# axiom_beta_plugin_module_eMMC_v0_1.net
KiCad netlist of a schematic drawn in EAGLE
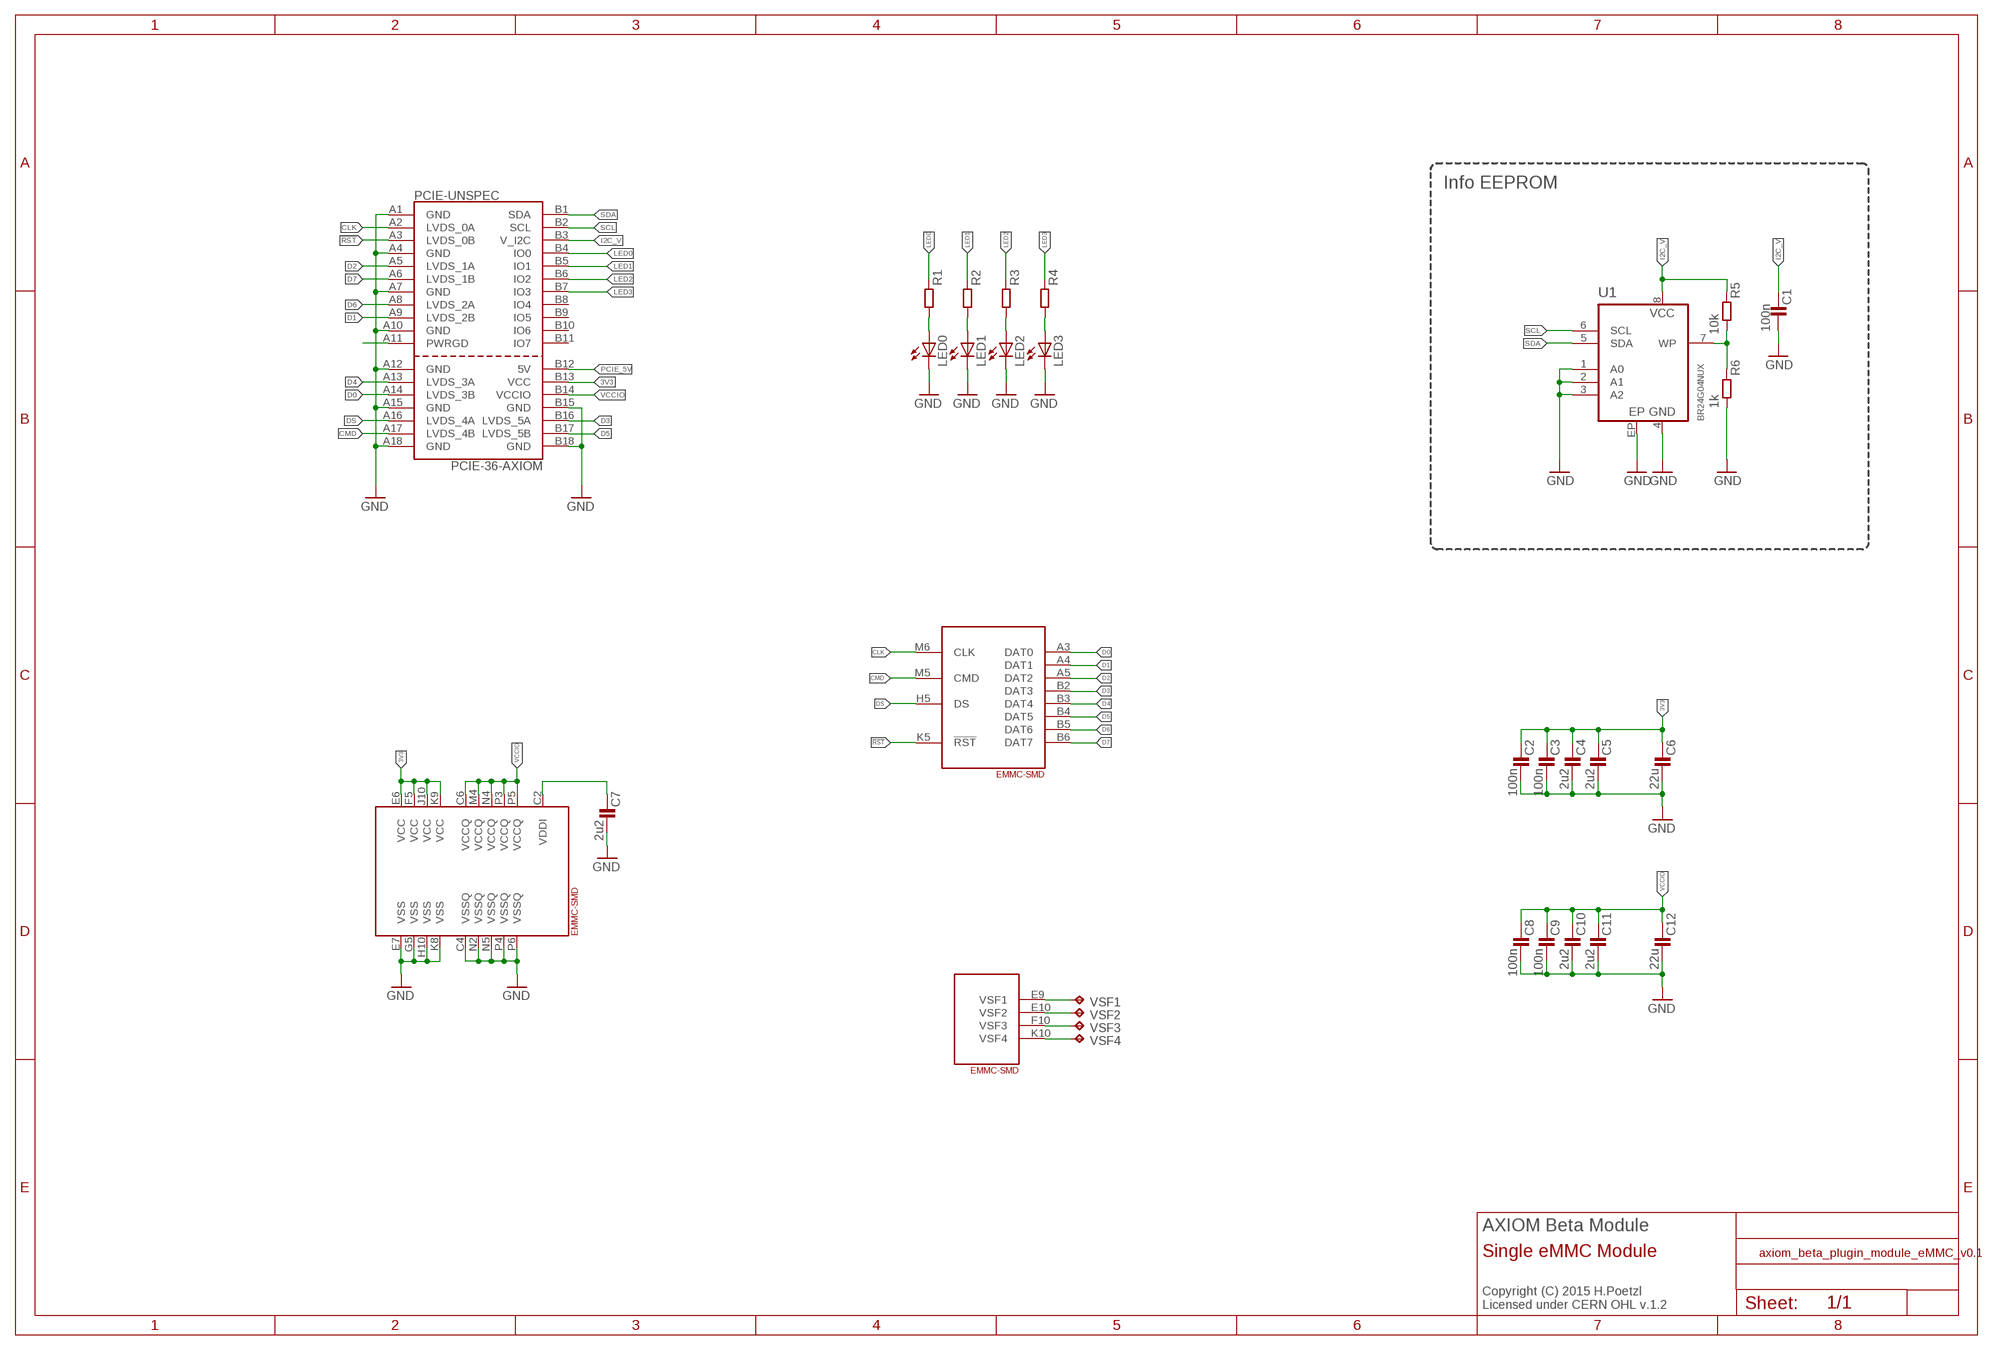
[diagram p0: schematic, sheet 1]

(export (version "E")
  (design (tool "Eeschema 10.0.6"))
  (components
    (comp (ref "C1")
      (value "100n")
      (footprint "eagle-import:0402-C")
      (libsource (lib "eagle-import") (part "C0402-C"))
    )
    (comp (ref "C2")
      (value "100n")
      (footprint "eagle-import:0201-C")
      (libsource (lib "eagle-import") (part "C0201-C"))
    )
    (comp (ref "C3")
      (value "100n")
      (footprint "eagle-import:0201-C")
      (libsource (lib "eagle-import") (part "C0201-C"))
    )
    (comp (ref "C4")
      (value "2u2")
      (footprint "eagle-import:0201-C")
      (libsource (lib "eagle-import") (part "C0201-C"))
    )
    (comp (ref "C5")
      (value "2u2")
      (footprint "eagle-import:0201-C")
      (libsource (lib "eagle-import") (part "C0201-C"))
    )
    (comp (ref "C6")
      (value "22u")
      (footprint "eagle-import:0805-C")
      (libsource (lib "eagle-import") (part "C0805-C"))
    )
    (comp (ref "C7")
      (value "2u2")
      (footprint "eagle-import:0201-C")
      (libsource (lib "eagle-import") (part "C0201-C"))
    )
    (comp (ref "C8")
      (value "100n")
      (footprint "eagle-import:0201-C")
      (libsource (lib "eagle-import") (part "C0201-C"))
    )
    (comp (ref "C9")
      (value "100n")
      (footprint "eagle-import:0201-C")
      (libsource (lib "eagle-import") (part "C0201-C"))
    )
    (comp (ref "C10")
      (value "2u2")
      (footprint "eagle-import:0201-C")
      (libsource (lib "eagle-import") (part "C0201-C"))
    )
    (comp (ref "C11")
      (value "2u2")
      (footprint "eagle-import:0201-C")
      (libsource (lib "eagle-import") (part "C0201-C"))
    )
    (comp (ref "C12")
      (value "22u")
      (footprint "eagle-import:0805-C")
      (libsource (lib "eagle-import") (part "C0805-C"))
    )
    (comp (ref "LED0")
      (value "LED")
      (footprint "eagle-import:CHIPLED_0603")
      (libsource (lib "eagle-import") (part "LED"))
    )
    (comp (ref "LED1")
      (value "LED")
      (footprint "eagle-import:CHIPLED_0603")
      (libsource (lib "eagle-import") (part "LED"))
    )
    (comp (ref "LED2")
      (value "LED")
      (footprint "eagle-import:CHIPLED_0603")
      (libsource (lib "eagle-import") (part "LED"))
    )
    (comp (ref "LED3")
      (value "LED")
      (footprint "eagle-import:CHIPLED_0603")
      (libsource (lib "eagle-import") (part "LED"))
    )
    (comp (ref "PCIE-UNSPEC")
      (value "PCIE-36-AXIOM")
      (footprint "eagle-import:PCIE-36-AXIOM")
      (libsource (lib "eagle-import") (part "PCIE-36-AXIOM"))
    )
    (comp (ref "R1")
      (value "R0402-C")
      (footprint "eagle-import:0402-C")
      (libsource (lib "eagle-import") (part "R0402-C"))
    )
    (comp (ref "R2")
      (value "R0402-C")
      (footprint "eagle-import:0402-C")
      (libsource (lib "eagle-import") (part "R0402-C"))
    )
    (comp (ref "R3")
      (value "R0402-C")
      (footprint "eagle-import:0402-C")
      (libsource (lib "eagle-import") (part "R0402-C"))
    )
    (comp (ref "R4")
      (value "R0402-C")
      (footprint "eagle-import:0402-C")
      (libsource (lib "eagle-import") (part "R0402-C"))
    )
    (comp (ref "R5")
      (value "10k")
      (footprint "eagle-import:0402-C")
      (libsource (lib "eagle-import") (part "R0402-C"))
    )
    (comp (ref "R6")
      (value "1k")
      (footprint "eagle-import:0402-C")
      (libsource (lib "eagle-import") (part "R0402-C"))
    )
    (comp (ref "U$1")
      (value "EMMC-SMD")
      (footprint "eagle-import:FBGA153-SMD")
      (libsource (lib "eagle-import") (part "EMMC-SMD"))
    )
    (comp (ref "U1")
      (value "BR24G04NUX")
      (footprint "eagle-import:DFN200X300X100-9N")
      (libsource (lib "eagle-import") (part "BR24G04NUX"))
    )
    (comp (ref "VSF1")
      (value "TPTP06SQ")
      (footprint "eagle-import:TP06SQ")
      (libsource (lib "eagle-import") (part "TPTP06SQ"))
    )
    (comp (ref "VSF2")
      (value "TPTP06SQ")
      (footprint "eagle-import:TP06SQ")
      (libsource (lib "eagle-import") (part "TPTP06SQ"))
    )
    (comp (ref "VSF3")
      (value "TPTP06SQ")
      (footprint "eagle-import:TP06SQ")
      (libsource (lib "eagle-import") (part "TPTP06SQ"))
    )
    (comp (ref "VSF4")
      (value "TPTP06SQ")
      (footprint "eagle-import:TP06SQ")
      (libsource (lib "eagle-import") (part "TPTP06SQ"))
    )
  )
  (nets
    (net (code "1") (name "/~{RST}") (class "Default")
      (node (ref "PCIE-UNSPEC") (pin "A3") (pinfunction "LVDS_0B_A3") (pintype "passive"))
      (node (ref "U$1") (pin "K5") (pinfunction "~{RST}_K5") (pintype "input"))
    )
    (net (code "2") (name "3V3") (class "Default")
      (node (ref "C2") (pin "1") (pinfunction "1_1") (pintype "passive"))
      (node (ref "C3") (pin "1") (pinfunction "1_1") (pintype "passive"))
      (node (ref "C4") (pin "1") (pinfunction "1_1") (pintype "passive"))
      (node (ref "C5") (pin "1") (pinfunction "1_1") (pintype "passive"))
      (node (ref "C6") (pin "1") (pinfunction "1_1") (pintype "passive"))
      (node (ref "PCIE-UNSPEC") (pin "B13") (pinfunction "VCC_B13") (pintype "passive"))
      (node (ref "U$1") (pin "E6") (pinfunction "VCC_E6") (pintype "power_in"))
      (node (ref "U$1") (pin "F5") (pinfunction "VCC_F5") (pintype "power_in"))
      (node (ref "U$1") (pin "J10") (pinfunction "VCC_J10") (pintype "power_in"))
      (node (ref "U$1") (pin "K9") (pinfunction "VCC_K9") (pintype "power_in"))
    )
    (net (code "3") (name "CLK") (class "Default")
      (node (ref "PCIE-UNSPEC") (pin "A2") (pinfunction "LVDS_0A_A2") (pintype "passive"))
      (node (ref "U$1") (pin "M6") (pinfunction "CLK_M6") (pintype "input"))
    )
    (net (code "4") (name "CMD") (class "Default")
      (node (ref "PCIE-UNSPEC") (pin "A17") (pinfunction "LVDS_4B_A17") (pintype "passive"))
      (node (ref "U$1") (pin "M5") (pinfunction "CMD_M5") (pintype "input"))
    )
    (net (code "5") (name "D0") (class "Default")
      (node (ref "PCIE-UNSPEC") (pin "A14") (pinfunction "LVDS_3B_A14") (pintype "passive"))
      (node (ref "U$1") (pin "A3") (pinfunction "DAT0_A3") (pintype "bidirectional"))
    )
    (net (code "6") (name "D1") (class "Default")
      (node (ref "PCIE-UNSPEC") (pin "A9") (pinfunction "LVDS_2B_A9") (pintype "passive"))
      (node (ref "U$1") (pin "A4") (pinfunction "DAT1_A4") (pintype "bidirectional"))
    )
    (net (code "7") (name "D2") (class "Default")
      (node (ref "PCIE-UNSPEC") (pin "A5") (pinfunction "LVDS_1A_A5") (pintype "passive"))
      (node (ref "U$1") (pin "A5") (pinfunction "DAT2_A5") (pintype "bidirectional"))
    )
    (net (code "8") (name "D3") (class "Default")
      (node (ref "PCIE-UNSPEC") (pin "B16") (pinfunction "LVDS_5A_B16") (pintype "passive"))
      (node (ref "U$1") (pin "B2") (pinfunction "DAT3_B2") (pintype "bidirectional"))
    )
    (net (code "9") (name "D4") (class "Default")
      (node (ref "PCIE-UNSPEC") (pin "A13") (pinfunction "LVDS_3A_A13") (pintype "passive"))
      (node (ref "U$1") (pin "B3") (pinfunction "DAT4_B3") (pintype "bidirectional"))
    )
    (net (code "10") (name "D5") (class "Default")
      (node (ref "PCIE-UNSPEC") (pin "B17") (pinfunction "LVDS_5B_B17") (pintype "passive"))
      (node (ref "U$1") (pin "B4") (pinfunction "DAT5_B4") (pintype "bidirectional"))
    )
    (net (code "11") (name "D6") (class "Default")
      (node (ref "PCIE-UNSPEC") (pin "A8") (pinfunction "LVDS_2A_A8") (pintype "passive"))
      (node (ref "U$1") (pin "B5") (pinfunction "DAT6_B5") (pintype "bidirectional"))
    )
    (net (code "12") (name "D7") (class "Default")
      (node (ref "PCIE-UNSPEC") (pin "A6") (pinfunction "LVDS_1B_A6") (pintype "passive"))
      (node (ref "U$1") (pin "B6") (pinfunction "DAT7_B6") (pintype "bidirectional"))
    )
    (net (code "13") (name "DS") (class "Default")
      (node (ref "PCIE-UNSPEC") (pin "A16") (pinfunction "LVDS_4A_A16") (pintype "passive"))
      (node (ref "U$1") (pin "H5") (pinfunction "DS_H5") (pintype "output"))
    )
    (net (code "14") (name "GND") (class "Default")
      (node (ref "C1") (pin "2") (pinfunction "2_2") (pintype "passive"))
      (node (ref "C10") (pin "2") (pinfunction "2_2") (pintype "passive"))
      (node (ref "C11") (pin "2") (pinfunction "2_2") (pintype "passive"))
      (node (ref "C12") (pin "2") (pinfunction "2_2") (pintype "passive"))
      (node (ref "C2") (pin "2") (pinfunction "2_2") (pintype "passive"))
      (node (ref "C3") (pin "2") (pinfunction "2_2") (pintype "passive"))
      (node (ref "C4") (pin "2") (pinfunction "2_2") (pintype "passive"))
      (node (ref "C5") (pin "2") (pinfunction "2_2") (pintype "passive"))
      (node (ref "C6") (pin "2") (pinfunction "2_2") (pintype "passive"))
      (node (ref "C7") (pin "2") (pinfunction "2_2") (pintype "passive"))
      (node (ref "C8") (pin "2") (pinfunction "2_2") (pintype "passive"))
      (node (ref "C9") (pin "2") (pinfunction "2_2") (pintype "passive"))
      (node (ref "LED0") (pin "C") (pinfunction "C_C") (pintype "passive"))
      (node (ref "LED1") (pin "C") (pinfunction "C_C") (pintype "passive"))
      (node (ref "LED2") (pin "C") (pinfunction "C_C") (pintype "passive"))
      (node (ref "LED3") (pin "C") (pinfunction "C_C") (pintype "passive"))
      (node (ref "PCIE-UNSPEC") (pin "A1") (pinfunction "GND_A1") (pintype "passive"))
      (node (ref "PCIE-UNSPEC") (pin "A10") (pinfunction "GND_A10") (pintype "passive"))
      (node (ref "PCIE-UNSPEC") (pin "A12") (pinfunction "GND_A12") (pintype "passive"))
      (node (ref "PCIE-UNSPEC") (pin "A15") (pinfunction "GND_A15") (pintype "passive"))
      (node (ref "PCIE-UNSPEC") (pin "A18") (pinfunction "GND_A18") (pintype "passive"))
      (node (ref "PCIE-UNSPEC") (pin "A4") (pinfunction "GND_A4") (pintype "passive"))
      (node (ref "PCIE-UNSPEC") (pin "A7") (pinfunction "GND_A7") (pintype "passive"))
      (node (ref "PCIE-UNSPEC") (pin "B15") (pinfunction "GND_B15") (pintype "passive"))
      (node (ref "PCIE-UNSPEC") (pin "B18") (pinfunction "GND_B18") (pintype "passive"))
      (node (ref "R6") (pin "2") (pinfunction "2_2") (pintype "passive"))
      (node (ref "U$1") (pin "C4") (pinfunction "VSSQ_C4") (pintype "power_in"))
      (node (ref "U$1") (pin "E7") (pinfunction "VSS_E7") (pintype "power_in"))
      (node (ref "U$1") (pin "G5") (pinfunction "VSS_G5") (pintype "power_in"))
      (node (ref "U$1") (pin "H10") (pinfunction "VSS_H10") (pintype "power_in"))
      (node (ref "U$1") (pin "K8") (pinfunction "VSS_K8") (pintype "power_in"))
      (node (ref "U$1") (pin "N2") (pinfunction "VSSQ_N2") (pintype "power_in"))
      (node (ref "U$1") (pin "N5") (pinfunction "VSSQ_N5") (pintype "power_in"))
      (node (ref "U$1") (pin "P4") (pinfunction "VSSQ_P4") (pintype "power_in"))
      (node (ref "U$1") (pin "P6") (pinfunction "VSSQ_P6") (pintype "power_in"))
      (node (ref "U1") (pin "1") (pinfunction "A0_1") (pintype "input"))
      (node (ref "U1") (pin "2") (pinfunction "A1_2") (pintype "input"))
      (node (ref "U1") (pin "3") (pinfunction "A2_3") (pintype "input"))
      (node (ref "U1") (pin "4") (pinfunction "GND_4") (pintype "passive"))
      (node (ref "U1") (pin "EP") (pinfunction "EP_EP") (pintype "passive"))
    )
    (net (code "15") (name "I2C_V") (class "Default")
      (node (ref "C1") (pin "1") (pinfunction "1_1") (pintype "passive"))
      (node (ref "PCIE-UNSPEC") (pin "B3") (pinfunction "V_I2C_B3") (pintype "passive"))
      (node (ref "R5") (pin "1") (pinfunction "1_1") (pintype "passive"))
      (node (ref "U1") (pin "8") (pinfunction "VCC_8") (pintype "power_in"))
    )
    (net (code "16") (name "LED0") (class "Default")
      (node (ref "PCIE-UNSPEC") (pin "B4") (pinfunction "IO0_B4") (pintype "passive"))
      (node (ref "R1") (pin "1") (pinfunction "1_1") (pintype "passive"))
    )
    (net (code "17") (name "LED1") (class "Default")
      (node (ref "PCIE-UNSPEC") (pin "B5") (pinfunction "IO1_B5") (pintype "passive"))
      (node (ref "R2") (pin "1") (pinfunction "1_1") (pintype "passive"))
    )
    (net (code "18") (name "LED2") (class "Default")
      (node (ref "PCIE-UNSPEC") (pin "B6") (pinfunction "IO2_B6") (pintype "passive"))
      (node (ref "R3") (pin "1") (pinfunction "1_1") (pintype "passive"))
    )
    (net (code "19") (name "LED3") (class "Default")
      (node (ref "PCIE-UNSPEC") (pin "B7") (pinfunction "IO3_B7") (pintype "passive"))
      (node (ref "R4") (pin "1") (pinfunction "1_1") (pintype "passive"))
    )
    (net (code "20") (name "Net-(LED0-PadA)") (class "Default")
      (node (ref "LED0") (pin "A") (pinfunction "A_A") (pintype "passive"))
      (node (ref "R1") (pin "2") (pinfunction "2_2") (pintype "passive"))
    )
    (net (code "21") (name "Net-(LED1-PadA)") (class "Default")
      (node (ref "LED1") (pin "A") (pinfunction "A_A") (pintype "passive"))
      (node (ref "R2") (pin "2") (pinfunction "2_2") (pintype "passive"))
    )
    (net (code "22") (name "Net-(LED2-PadA)") (class "Default")
      (node (ref "LED2") (pin "A") (pinfunction "A_A") (pintype "passive"))
      (node (ref "R3") (pin "2") (pinfunction "2_2") (pintype "passive"))
    )
    (net (code "23") (name "Net-(LED3-PadA)") (class "Default")
      (node (ref "LED3") (pin "A") (pinfunction "A_A") (pintype "passive"))
      (node (ref "R4") (pin "2") (pinfunction "2_2") (pintype "passive"))
    )
    (net (code "24") (name "Net-(U$1B-VDDI)") (class "Default")
      (node (ref "C7") (pin "1") (pinfunction "1_1") (pintype "passive"))
      (node (ref "U$1") (pin "C2") (pinfunction "VDDI_C2") (pintype "power_in"))
    )
    (net (code "25") (name "Net-(U$1C-VSF1)") (class "Default")
      (node (ref "U$1") (pin "E9") (pinfunction "VSF1_E9") (pintype "bidirectional"))
      (node (ref "VSF1") (pin "TP") (pinfunction "TP_TP") (pintype "input"))
    )
    (net (code "26") (name "Net-(U$1C-VSF2)") (class "Default")
      (node (ref "U$1") (pin "E10") (pinfunction "VSF2_E10") (pintype "bidirectional"))
      (node (ref "VSF2") (pin "TP") (pinfunction "TP_TP") (pintype "input"))
    )
    (net (code "27") (name "Net-(U$1C-VSF3)") (class "Default")
      (node (ref "U$1") (pin "F10") (pinfunction "VSF3_F10") (pintype "bidirectional"))
      (node (ref "VSF3") (pin "TP") (pinfunction "TP_TP") (pintype "input"))
    )
    (net (code "28") (name "Net-(U$1C-VSF4)") (class "Default")
      (node (ref "U$1") (pin "K10") (pinfunction "VSF4_K10") (pintype "bidirectional"))
      (node (ref "VSF4") (pin "TP") (pinfunction "TP_TP") (pintype "input"))
    )
    (net (code "29") (name "Net-(U1-WP)") (class "Default")
      (node (ref "R5") (pin "2") (pinfunction "2_2") (pintype "passive"))
      (node (ref "R6") (pin "1") (pinfunction "1_1") (pintype "passive"))
      (node (ref "U1") (pin "7") (pinfunction "WP_7") (pintype "input"))
    )
    (net (code "30") (name "PCIE_5V") (class "Default")
      (node (ref "PCIE-UNSPEC") (pin "B12") (pinfunction "5V_B12") (pintype "passive"))
    )
    (net (code "31") (name "SCL") (class "Default")
      (node (ref "PCIE-UNSPEC") (pin "B2") (pinfunction "SCL_B2") (pintype "passive"))
      (node (ref "U1") (pin "6") (pinfunction "SCL_6") (pintype "input"))
    )
    (net (code "32") (name "SDA") (class "Default")
      (node (ref "PCIE-UNSPEC") (pin "B1") (pinfunction "SDA_B1") (pintype "passive"))
      (node (ref "U1") (pin "5") (pinfunction "SDA_5") (pintype "bidirectional"))
    )
    (net (code "33") (name "VCCIO") (class "Default")
      (node (ref "C10") (pin "1") (pinfunction "1_1") (pintype "passive"))
      (node (ref "C11") (pin "1") (pinfunction "1_1") (pintype "passive"))
      (node (ref "C12") (pin "1") (pinfunction "1_1") (pintype "passive"))
      (node (ref "C8") (pin "1") (pinfunction "1_1") (pintype "passive"))
      (node (ref "C9") (pin "1") (pinfunction "1_1") (pintype "passive"))
      (node (ref "PCIE-UNSPEC") (pin "B14") (pinfunction "VCCIO_B14") (pintype "passive"))
      (node (ref "U$1") (pin "C6") (pinfunction "VCCQ_C6") (pintype "power_in"))
      (node (ref "U$1") (pin "M4") (pinfunction "VCCQ_M4") (pintype "power_in"))
      (node (ref "U$1") (pin "N4") (pinfunction "VCCQ_N4") (pintype "power_in"))
      (node (ref "U$1") (pin "P3") (pinfunction "VCCQ_P3") (pintype "power_in"))
      (node (ref "U$1") (pin "P5") (pinfunction "VCCQ_P5") (pintype "power_in"))
    )
    (net (code "34") (name "unconnected-(PCIE-UNSPEC-IO4-PadB8)") (class "Default")
      (node (ref "PCIE-UNSPEC") (pin "B8") (pinfunction "IO4_B8") (pintype "passive"))
    )
    (net (code "35") (name "unconnected-(PCIE-UNSPEC-IO5-PadB9)") (class "Default")
      (node (ref "PCIE-UNSPEC") (pin "B9") (pinfunction "IO5_B9") (pintype "passive"))
    )
    (net (code "36") (name "unconnected-(PCIE-UNSPEC-IO6-PadB10)") (class "Default")
      (node (ref "PCIE-UNSPEC") (pin "B10") (pinfunction "IO6_B10") (pintype "passive"))
    )
    (net (code "37") (name "unconnected-(PCIE-UNSPEC-IO7-PadB11)") (class "Default")
      (node (ref "PCIE-UNSPEC") (pin "B11") (pinfunction "IO7_B11") (pintype "passive"))
    )
    (net (code "38") (name "unconnected-(PCIE-UNSPEC-PWRGD-PadA11)") (class "Default")
      (node (ref "PCIE-UNSPEC") (pin "A11") (pinfunction "PWRGD_A11") (pintype "passive"))
    )
  )
)
